# macaron.net
KiCad netlist of a schematic drawn in EAGLE
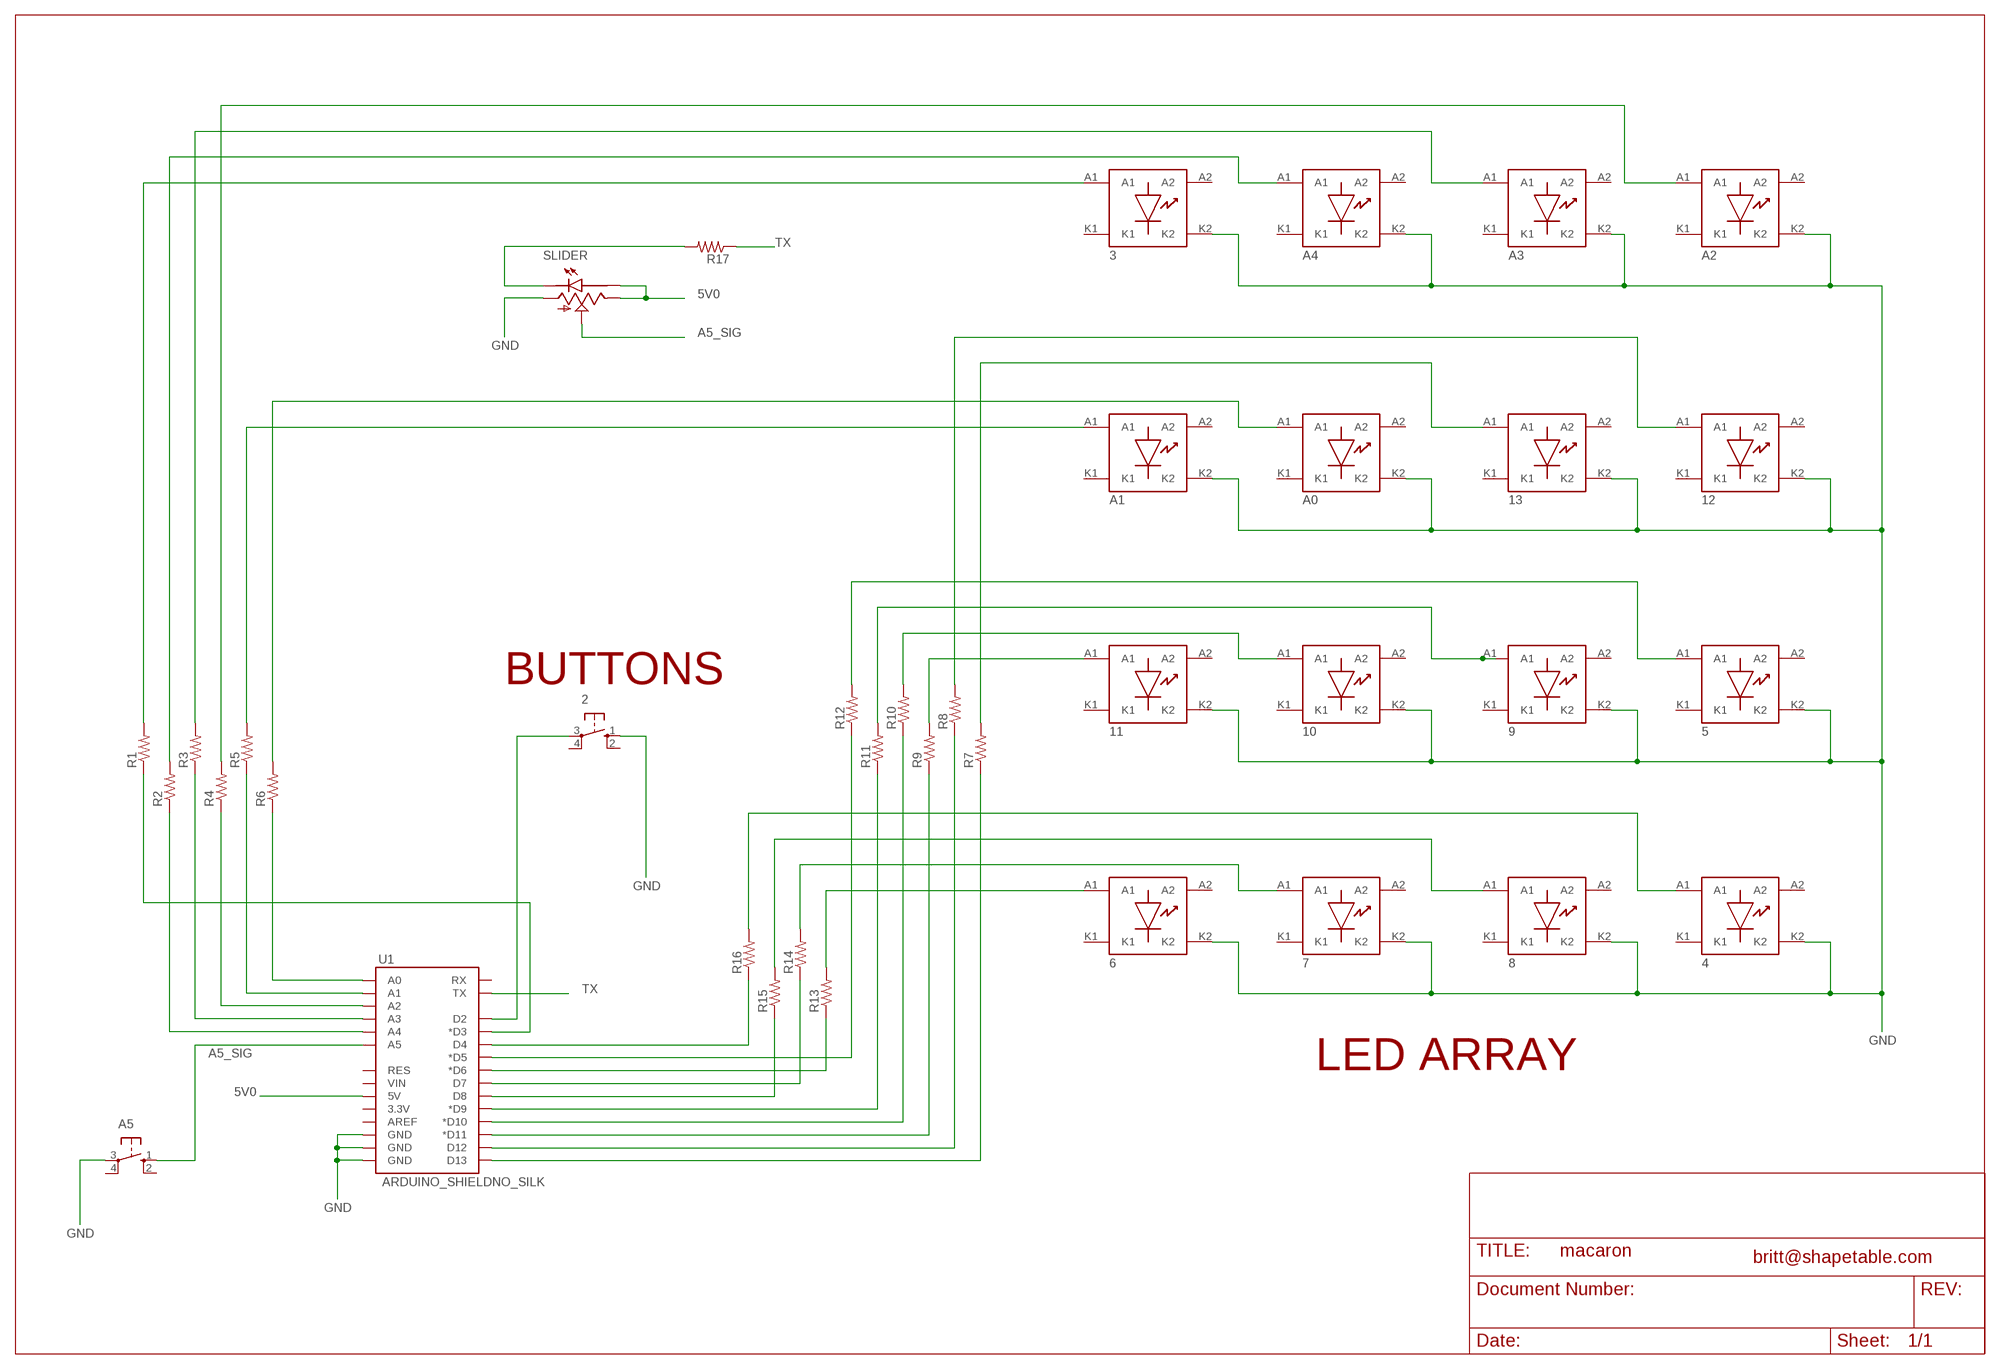
[diagram p0: schematic, sheet 1]

(export (version "E")
  (design (tool "Eeschema 10.0.6"))
  (components
    (comp (ref "2")
      (value "10-XX")
      (footprint "eagle-import:B3F-10XX")
      (fields (field (name "MPN") "B3F-1000"))
      (libsource (lib "eagle-import") (part "10-XX"))
    )
    (comp (ref "3")
      (value "LED_SMT")
      (footprint "eagle-import:AVAGO-SMT-LED")
      (libsource (lib "eagle-import") (part "LED_SMT"))
    )
    (comp (ref "4")
      (value "LED_SMT")
      (footprint "eagle-import:AVAGO-SMT-LED")
      (libsource (lib "eagle-import") (part "LED_SMT"))
    )
    (comp (ref "5")
      (value "LED_SMT")
      (footprint "eagle-import:AVAGO-SMT-LED")
      (libsource (lib "eagle-import") (part "LED_SMT"))
    )
    (comp (ref "6")
      (value "LED_SMT")
      (footprint "eagle-import:AVAGO-SMT-LED")
      (libsource (lib "eagle-import") (part "LED_SMT"))
    )
    (comp (ref "7")
      (value "LED_SMT")
      (footprint "eagle-import:AVAGO-SMT-LED")
      (libsource (lib "eagle-import") (part "LED_SMT"))
    )
    (comp (ref "8")
      (value "LED_SMT")
      (footprint "eagle-import:AVAGO-SMT-LED")
      (libsource (lib "eagle-import") (part "LED_SMT"))
    )
    (comp (ref "9")
      (value "LED_SMT")
      (footprint "eagle-import:AVAGO-SMT-LED")
      (libsource (lib "eagle-import") (part "LED_SMT"))
    )
    (comp (ref "10")
      (value "LED_SMT")
      (footprint "eagle-import:AVAGO-SMT-LED")
      (libsource (lib "eagle-import") (part "LED_SMT"))
    )
    (comp (ref "11")
      (value "LED_SMT")
      (footprint "eagle-import:AVAGO-SMT-LED")
      (libsource (lib "eagle-import") (part "LED_SMT"))
    )
    (comp (ref "12")
      (value "LED_SMT")
      (footprint "eagle-import:AVAGO-SMT-LED")
      (libsource (lib "eagle-import") (part "LED_SMT"))
    )
    (comp (ref "13")
      (value "LED_SMT")
      (footprint "eagle-import:AVAGO-SMT-LED")
      (libsource (lib "eagle-import") (part "LED_SMT"))
    )
    (comp (ref "A0")
      (value "LED_SMT")
      (footprint "eagle-import:AVAGO-SMT-LED")
      (libsource (lib "eagle-import") (part "LED_SMT"))
    )
    (comp (ref "A1")
      (value "LED_SMT")
      (footprint "eagle-import:AVAGO-SMT-LED")
      (libsource (lib "eagle-import") (part "LED_SMT"))
    )
    (comp (ref "A2")
      (value "LED_SMT")
      (footprint "eagle-import:AVAGO-SMT-LED")
      (libsource (lib "eagle-import") (part "LED_SMT"))
    )
    (comp (ref "A3")
      (value "LED_SMT")
      (footprint "eagle-import:AVAGO-SMT-LED")
      (libsource (lib "eagle-import") (part "LED_SMT"))
    )
    (comp (ref "A4")
      (value "LED_SMT")
      (footprint "eagle-import:AVAGO-SMT-LED")
      (libsource (lib "eagle-import") (part "LED_SMT"))
    )
    (comp (ref "A5")
      (value "10-XX")
      (footprint "eagle-import:B3F-10XX")
      (fields (field (name "MPN") "B3F-1000"))
      (libsource (lib "eagle-import") (part "10-XX"))
    )
    (comp (ref "R1")
      (value "R-US_0204/7")
      (footprint "eagle-import:0204_7")
      (libsource (lib "eagle-import") (part "R-US_0204/7"))
    )
    (comp (ref "R2")
      (value "R-US_0204/7")
      (footprint "eagle-import:0204_7")
      (libsource (lib "eagle-import") (part "R-US_0204/7"))
    )
    (comp (ref "R3")
      (value "R-US_0204/7")
      (footprint "eagle-import:0204_7")
      (libsource (lib "eagle-import") (part "R-US_0204/7"))
    )
    (comp (ref "R4")
      (value "R-US_0204/7")
      (footprint "eagle-import:0204_7")
      (libsource (lib "eagle-import") (part "R-US_0204/7"))
    )
    (comp (ref "R5")
      (value "R-US_0204/7")
      (footprint "eagle-import:0204_7")
      (libsource (lib "eagle-import") (part "R-US_0204/7"))
    )
    (comp (ref "R6")
      (value "R-US_0204/7")
      (footprint "eagle-import:0204_7")
      (libsource (lib "eagle-import") (part "R-US_0204/7"))
    )
    (comp (ref "R7")
      (value "R-US_0204/7")
      (footprint "eagle-import:0204_7")
      (libsource (lib "eagle-import") (part "R-US_0204/7"))
    )
    (comp (ref "R8")
      (value "R-US_0204/7")
      (footprint "eagle-import:0204_7")
      (libsource (lib "eagle-import") (part "R-US_0204/7"))
    )
    (comp (ref "R9")
      (value "R-US_0204/7")
      (footprint "eagle-import:0204_7")
      (libsource (lib "eagle-import") (part "R-US_0204/7"))
    )
    (comp (ref "R10")
      (value "R-US_0204/7")
      (footprint "eagle-import:0204_7")
      (libsource (lib "eagle-import") (part "R-US_0204/7"))
    )
    (comp (ref "R11")
      (value "R-US_0204/7")
      (footprint "eagle-import:0204_7")
      (libsource (lib "eagle-import") (part "R-US_0204/7"))
    )
    (comp (ref "R12")
      (value "R-US_0204/7")
      (footprint "eagle-import:0204_7")
      (libsource (lib "eagle-import") (part "R-US_0204/7"))
    )
    (comp (ref "R13")
      (value "R-US_0204/7")
      (footprint "eagle-import:0204_7")
      (libsource (lib "eagle-import") (part "R-US_0204/7"))
    )
    (comp (ref "R14")
      (value "R-US_0204/7")
      (footprint "eagle-import:0204_7")
      (libsource (lib "eagle-import") (part "R-US_0204/7"))
    )
    (comp (ref "R15")
      (value "R-US_0204/7")
      (footprint "eagle-import:0204_7")
      (libsource (lib "eagle-import") (part "R-US_0204/7"))
    )
    (comp (ref "R16")
      (value "R-US_0204/7")
      (footprint "eagle-import:0204_7")
      (libsource (lib "eagle-import") (part "R-US_0204/7"))
    )
    (comp (ref "R17")
      (value "R-US_0204/7")
      (footprint "eagle-import:0204_7")
      (libsource (lib "eagle-import") (part "R-US_0204/7"))
    )
    (comp (ref "SLIDER")
      (value "BOURNS_LED_SLIDER")
      (footprint "eagle-import:BOURNS_45MM_LED_SLIDE_POT")
      (libsource (lib "eagle-import") (part "BOURNS_LED_SLIDER"))
    )
    (comp (ref "U1")
      (value "ARDUINO_SHIELDNO_SILK")
      (footprint "eagle-import:DUEMILANOVE_VIAS")
      (libsource (lib "eagle-import") (part "ARDUINO_SHIELDNO_SILK"))
    )
  )
  (nets
    (net (code "1") (name "/5V0") (class "Default")
      (node (ref "SLIDER") (pin "HIGH_END") (pinfunction "HIGH_HIGH_END") (pintype "passive"))
      (node (ref "SLIDER") (pin "LED+") (pinfunction "A1_LED+") (pintype "passive"))
      (node (ref "U1") (pin "5V") (pinfunction "5V_5V") (pintype "bidirectional"))
    )
    (net (code "2") (name "/A5_SIG") (class "Default")
      (node (ref "A5") (pin "1") (pinfunction "S_1") (pintype "passive"))
      (node (ref "SLIDER") (pin "WIPER") (pinfunction "WIPER_WIPER") (pintype "passive"))
      (node (ref "U1") (pin "A5") (pinfunction "A5_A5") (pintype "bidirectional"))
    )
    (net (code "3") (name "/GND") (class "Default")
      (node (ref "10") (pin "K2") (pinfunction "K2_K2") (pintype "passive"))
      (node (ref "11") (pin "K2") (pinfunction "K2_K2") (pintype "passive"))
      (node (ref "12") (pin "K2") (pinfunction "K2_K2") (pintype "passive"))
      (node (ref "13") (pin "K2") (pinfunction "K2_K2") (pintype "passive"))
      (node (ref "2") (pin "1") (pinfunction "S_1") (pintype "passive"))
      (node (ref "3") (pin "K2") (pinfunction "K2_K2") (pintype "passive"))
      (node (ref "4") (pin "K2") (pinfunction "K2_K2") (pintype "passive"))
      (node (ref "5") (pin "K2") (pinfunction "K2_K2") (pintype "passive"))
      (node (ref "6") (pin "K2") (pinfunction "K2_K2") (pintype "passive"))
      (node (ref "7") (pin "K2") (pinfunction "K2_K2") (pintype "passive"))
      (node (ref "8") (pin "K2") (pinfunction "K2_K2") (pintype "passive"))
      (node (ref "9") (pin "K2") (pinfunction "K2_K2") (pintype "passive"))
      (node (ref "A0") (pin "K2") (pinfunction "K2_K2") (pintype "passive"))
      (node (ref "A1") (pin "K2") (pinfunction "K2_K2") (pintype "passive"))
      (node (ref "A2") (pin "K2") (pinfunction "K2_K2") (pintype "passive"))
      (node (ref "A3") (pin "K2") (pinfunction "K2_K2") (pintype "passive"))
      (node (ref "A4") (pin "K2") (pinfunction "K2_K2") (pintype "passive"))
      (node (ref "A5") (pin "3") (pinfunction "P_3") (pintype "passive"))
      (node (ref "SLIDER") (pin "LOW_END") (pinfunction "LOW_LOW_END") (pintype "passive"))
      (node (ref "U1") (pin "GND@0") (pinfunction "GND_GND@0") (pintype "bidirectional"))
      (node (ref "U1") (pin "GND@1") (pinfunction "GND_GND@1") (pintype "bidirectional"))
      (node (ref "U1") (pin "GND@2") (pinfunction "GND_GND@2") (pintype "bidirectional"))
    )
    (net (code "4") (name "/TX") (class "Default")
      (node (ref "R17") (pin "1") (pinfunction "1_1") (pintype "passive"))
      (node (ref "U1") (pin "TX") (pinfunction "TX_TX") (pintype "bidirectional"))
    )
    (net (code "5") (name "Net-(2-P)") (class "Default")
      (node (ref "2") (pin "3") (pinfunction "P_3") (pintype "passive"))
      (node (ref "U1") (pin "D2") (pinfunction "D2_D2") (pintype "bidirectional"))
    )
    (net (code "6") (name "Net-(3-PadA1)") (class "Default")
      (node (ref "3") (pin "A1") (pinfunction "A1_A1") (pintype "passive"))
      (node (ref "R1") (pin "2") (pinfunction "2_2") (pintype "passive"))
    )
    (net (code "7") (name "Net-(4-PadA1)") (class "Default")
      (node (ref "4") (pin "A1") (pinfunction "A1_A1") (pintype "passive"))
      (node (ref "R16") (pin "2") (pinfunction "2_2") (pintype "passive"))
    )
    (net (code "8") (name "Net-(5-PadA1)") (class "Default")
      (node (ref "5") (pin "A1") (pinfunction "A1_A1") (pintype "passive"))
      (node (ref "R12") (pin "2") (pinfunction "2_2") (pintype "passive"))
    )
    (net (code "9") (name "Net-(6-PadA1)") (class "Default")
      (node (ref "6") (pin "A1") (pinfunction "A1_A1") (pintype "passive"))
      (node (ref "R13") (pin "2") (pinfunction "2_2") (pintype "passive"))
    )
    (net (code "10") (name "Net-(7-PadA1)") (class "Default")
      (node (ref "7") (pin "A1") (pinfunction "A1_A1") (pintype "passive"))
      (node (ref "R14") (pin "2") (pinfunction "2_2") (pintype "passive"))
    )
    (net (code "11") (name "Net-(8-PadA1)") (class "Default")
      (node (ref "8") (pin "A1") (pinfunction "A1_A1") (pintype "passive"))
      (node (ref "R15") (pin "2") (pinfunction "2_2") (pintype "passive"))
    )
    (net (code "12") (name "Net-(9-PadA1)") (class "Default")
      (node (ref "9") (pin "A1") (pinfunction "A1_A1") (pintype "passive"))
      (node (ref "R11") (pin "2") (pinfunction "2_2") (pintype "passive"))
    )
    (net (code "13") (name "Net-(10-PadA1)") (class "Default")
      (node (ref "10") (pin "A1") (pinfunction "A1_A1") (pintype "passive"))
      (node (ref "R10") (pin "2") (pinfunction "2_2") (pintype "passive"))
    )
    (net (code "14") (name "Net-(11-PadA1)") (class "Default")
      (node (ref "11") (pin "A1") (pinfunction "A1_A1") (pintype "passive"))
      (node (ref "R9") (pin "2") (pinfunction "2_2") (pintype "passive"))
    )
    (net (code "15") (name "Net-(12-PadA1)") (class "Default")
      (node (ref "12") (pin "A1") (pinfunction "A1_A1") (pintype "passive"))
      (node (ref "R8") (pin "2") (pinfunction "2_2") (pintype "passive"))
    )
    (net (code "16") (name "Net-(13-PadA1)") (class "Default")
      (node (ref "13") (pin "A1") (pinfunction "A1_A1") (pintype "passive"))
      (node (ref "R7") (pin "2") (pinfunction "2_2") (pintype "passive"))
    )
    (net (code "17") (name "Net-(A0-PadA1)") (class "Default")
      (node (ref "A0") (pin "A1") (pinfunction "A1_A1") (pintype "passive"))
      (node (ref "R6") (pin "2") (pinfunction "2_2") (pintype "passive"))
    )
    (net (code "18") (name "Net-(A1-PadA1)") (class "Default")
      (node (ref "A1") (pin "A1") (pinfunction "A1_A1") (pintype "passive"))
      (node (ref "R5") (pin "2") (pinfunction "2_2") (pintype "passive"))
    )
    (net (code "19") (name "Net-(A2-PadA1)") (class "Default")
      (node (ref "A2") (pin "A1") (pinfunction "A1_A1") (pintype "passive"))
      (node (ref "R4") (pin "2") (pinfunction "2_2") (pintype "passive"))
    )
    (net (code "20") (name "Net-(A3-PadA1)") (class "Default")
      (node (ref "A3") (pin "A1") (pinfunction "A1_A1") (pintype "passive"))
      (node (ref "R3") (pin "2") (pinfunction "2_2") (pintype "passive"))
    )
    (net (code "21") (name "Net-(A4-PadA1)") (class "Default")
      (node (ref "A4") (pin "A1") (pinfunction "A1_A1") (pintype "passive"))
      (node (ref "R2") (pin "2") (pinfunction "2_2") (pintype "passive"))
    )
    (net (code "22") (name "Net-(R2-Pad1)") (class "Default")
      (node (ref "R2") (pin "1") (pinfunction "1_1") (pintype "passive"))
      (node (ref "U1") (pin "A4") (pinfunction "A4_A4") (pintype "bidirectional"))
    )
    (net (code "23") (name "Net-(R3-Pad1)") (class "Default")
      (node (ref "R3") (pin "1") (pinfunction "1_1") (pintype "passive"))
      (node (ref "U1") (pin "A3") (pinfunction "A3_A3") (pintype "bidirectional"))
    )
    (net (code "24") (name "Net-(R4-Pad1)") (class "Default")
      (node (ref "R4") (pin "1") (pinfunction "1_1") (pintype "passive"))
      (node (ref "U1") (pin "A2") (pinfunction "A2_A2") (pintype "bidirectional"))
    )
    (net (code "25") (name "Net-(R5-Pad1)") (class "Default")
      (node (ref "R5") (pin "1") (pinfunction "1_1") (pintype "passive"))
      (node (ref "U1") (pin "A1") (pinfunction "A1_A1") (pintype "bidirectional"))
    )
    (net (code "26") (name "Net-(R6-Pad1)") (class "Default")
      (node (ref "R6") (pin "1") (pinfunction "1_1") (pintype "passive"))
      (node (ref "U1") (pin "A0") (pinfunction "A0_A0") (pintype "bidirectional"))
    )
    (net (code "27") (name "Net-(R7-Pad1)") (class "Default")
      (node (ref "R7") (pin "1") (pinfunction "1_1") (pintype "passive"))
      (node (ref "U1") (pin "D13") (pinfunction "D13_D13") (pintype "bidirectional"))
    )
    (net (code "28") (name "Net-(R8-Pad1)") (class "Default")
      (node (ref "R8") (pin "1") (pinfunction "1_1") (pintype "passive"))
      (node (ref "U1") (pin "D12") (pinfunction "D12_D12") (pintype "bidirectional"))
    )
    (net (code "29") (name "Net-(R14-Pad1)") (class "Default")
      (node (ref "R14") (pin "1") (pinfunction "1_1") (pintype "passive"))
      (node (ref "U1") (pin "D7") (pinfunction "D7_D7") (pintype "bidirectional"))
    )
    (net (code "30") (name "Net-(R15-Pad1)") (class "Default")
      (node (ref "R15") (pin "1") (pinfunction "1_1") (pintype "passive"))
      (node (ref "U1") (pin "D8") (pinfunction "D8_D8") (pintype "bidirectional"))
    )
    (net (code "31") (name "Net-(R16-Pad1)") (class "Default")
      (node (ref "R16") (pin "1") (pinfunction "1_1") (pintype "passive"))
      (node (ref "U1") (pin "D4") (pinfunction "D4_D4") (pintype "bidirectional"))
    )
    (net (code "32") (name "Net-(SLIDER-C)") (class "Default")
      (node (ref "R17") (pin "2") (pinfunction "2_2") (pintype "passive"))
      (node (ref "SLIDER") (pin "LED-") (pinfunction "C_LED-") (pintype "passive"))
    )
    (net (code "33") (name "Net-(U1-*D3)") (class "Default")
      (node (ref "R1") (pin "1") (pinfunction "1_1") (pintype "passive"))
      (node (ref "U1") (pin "D3") (pinfunction "*D3_D3") (pintype "bidirectional"))
    )
    (net (code "34") (name "Net-(U1-*D5)") (class "Default")
      (node (ref "R12") (pin "1") (pinfunction "1_1") (pintype "passive"))
      (node (ref "U1") (pin "D5") (pinfunction "*D5_D5") (pintype "bidirectional"))
    )
    (net (code "35") (name "Net-(U1-*D6)") (class "Default")
      (node (ref "R13") (pin "1") (pinfunction "1_1") (pintype "passive"))
      (node (ref "U1") (pin "D6") (pinfunction "*D6_D6") (pintype "bidirectional"))
    )
    (net (code "36") (name "Net-(U1-*D9)") (class "Default")
      (node (ref "R11") (pin "1") (pinfunction "1_1") (pintype "passive"))
      (node (ref "U1") (pin "D9") (pinfunction "*D9_D9") (pintype "bidirectional"))
    )
    (net (code "37") (name "Net-(U1-*D10)") (class "Default")
      (node (ref "R10") (pin "1") (pinfunction "1_1") (pintype "passive"))
      (node (ref "U1") (pin "D10") (pinfunction "*D10_D10") (pintype "bidirectional"))
    )
    (net (code "38") (name "Net-(U1-*D11)") (class "Default")
      (node (ref "R9") (pin "1") (pinfunction "1_1") (pintype "passive"))
      (node (ref "U1") (pin "D11") (pinfunction "*D11_D11") (pintype "bidirectional"))
    )
    (net (code "39") (name "unconnected-(2-P1-Pad4)") (class "Default")
      (node (ref "2") (pin "4") (pinfunction "P1_4") (pintype "passive"))
    )
    (net (code "40") (name "unconnected-(2-S1-Pad2)") (class "Default")
      (node (ref "2") (pin "2") (pinfunction "S1_2") (pintype "passive"))
    )
    (net (code "41") (name "unconnected-(3-PadA2)") (class "Default")
      (node (ref "3") (pin "A2") (pinfunction "A2_A2") (pintype "passive"))
    )
    (net (code "42") (name "unconnected-(3-PadK1)") (class "Default")
      (node (ref "3") (pin "K1") (pinfunction "K1_K1") (pintype "passive"))
    )
    (net (code "43") (name "unconnected-(4-PadA2)") (class "Default")
      (node (ref "4") (pin "A2") (pinfunction "A2_A2") (pintype "passive"))
    )
    (net (code "44") (name "unconnected-(4-PadK1)") (class "Default")
      (node (ref "4") (pin "K1") (pinfunction "K1_K1") (pintype "passive"))
    )
    (net (code "45") (name "unconnected-(5-PadA2)") (class "Default")
      (node (ref "5") (pin "A2") (pinfunction "A2_A2") (pintype "passive"))
    )
    (net (code "46") (name "unconnected-(5-PadK1)") (class "Default")
      (node (ref "5") (pin "K1") (pinfunction "K1_K1") (pintype "passive"))
    )
    (net (code "47") (name "unconnected-(6-PadA2)") (class "Default")
      (node (ref "6") (pin "A2") (pinfunction "A2_A2") (pintype "passive"))
    )
    (net (code "48") (name "unconnected-(6-PadK1)") (class "Default")
      (node (ref "6") (pin "K1") (pinfunction "K1_K1") (pintype "passive"))
    )
    (net (code "49") (name "unconnected-(7-PadA2)") (class "Default")
      (node (ref "7") (pin "A2") (pinfunction "A2_A2") (pintype "passive"))
    )
    (net (code "50") (name "unconnected-(7-PadK1)") (class "Default")
      (node (ref "7") (pin "K1") (pinfunction "K1_K1") (pintype "passive"))
    )
    (net (code "51") (name "unconnected-(8-PadA2)") (class "Default")
      (node (ref "8") (pin "A2") (pinfunction "A2_A2") (pintype "passive"))
    )
    (net (code "52") (name "unconnected-(8-PadK1)") (class "Default")
      (node (ref "8") (pin "K1") (pinfunction "K1_K1") (pintype "passive"))
    )
    (net (code "53") (name "unconnected-(9-PadA2)") (class "Default")
      (node (ref "9") (pin "A2") (pinfunction "A2_A2") (pintype "passive"))
    )
    (net (code "54") (name "unconnected-(9-PadK1)") (class "Default")
      (node (ref "9") (pin "K1") (pinfunction "K1_K1") (pintype "passive"))
    )
    (net (code "55") (name "unconnected-(10-PadA2)") (class "Default")
      (node (ref "10") (pin "A2") (pinfunction "A2_A2") (pintype "passive"))
    )
    (net (code "56") (name "unconnected-(10-PadK1)") (class "Default")
      (node (ref "10") (pin "K1") (pinfunction "K1_K1") (pintype "passive"))
    )
    (net (code "57") (name "unconnected-(11-PadA2)") (class "Default")
      (node (ref "11") (pin "A2") (pinfunction "A2_A2") (pintype "passive"))
    )
    (net (code "58") (name "unconnected-(11-PadK1)") (class "Default")
      (node (ref "11") (pin "K1") (pinfunction "K1_K1") (pintype "passive"))
    )
    (net (code "59") (name "unconnected-(12-PadA2)") (class "Default")
      (node (ref "12") (pin "A2") (pinfunction "A2_A2") (pintype "passive"))
    )
    (net (code "60") (name "unconnected-(12-PadK1)") (class "Default")
      (node (ref "12") (pin "K1") (pinfunction "K1_K1") (pintype "passive"))
    )
    (net (code "61") (name "unconnected-(13-PadA2)") (class "Default")
      (node (ref "13") (pin "A2") (pinfunction "A2_A2") (pintype "passive"))
    )
    (net (code "62") (name "unconnected-(13-PadK1)") (class "Default")
      (node (ref "13") (pin "K1") (pinfunction "K1_K1") (pintype "passive"))
    )
    (net (code "63") (name "unconnected-(A0-PadA2)") (class "Default")
      (node (ref "A0") (pin "A2") (pinfunction "A2_A2") (pintype "passive"))
    )
    (net (code "64") (name "unconnected-(A0-PadK1)") (class "Default")
      (node (ref "A0") (pin "K1") (pinfunction "K1_K1") (pintype "passive"))
    )
    (net (code "65") (name "unconnected-(A1-PadA2)") (class "Default")
      (node (ref "A1") (pin "A2") (pinfunction "A2_A2") (pintype "passive"))
    )
    (net (code "66") (name "unconnected-(A1-PadK1)") (class "Default")
      (node (ref "A1") (pin "K1") (pinfunction "K1_K1") (pintype "passive"))
    )
    (net (code "67") (name "unconnected-(A2-PadA2)") (class "Default")
      (node (ref "A2") (pin "A2") (pinfunction "A2_A2") (pintype "passive"))
    )
    (net (code "68") (name "unconnected-(A2-PadK1)") (class "Default")
      (node (ref "A2") (pin "K1") (pinfunction "K1_K1") (pintype "passive"))
    )
    (net (code "69") (name "unconnected-(A3-PadA2)") (class "Default")
      (node (ref "A3") (pin "A2") (pinfunction "A2_A2") (pintype "passive"))
    )
    (net (code "70") (name "unconnected-(A3-PadK1)") (class "Default")
      (node (ref "A3") (pin "K1") (pinfunction "K1_K1") (pintype "passive"))
    )
    (net (code "71") (name "unconnected-(A4-PadA2)") (class "Default")
      (node (ref "A4") (pin "A2") (pinfunction "A2_A2") (pintype "passive"))
    )
    (net (code "72") (name "unconnected-(A4-PadK1)") (class "Default")
      (node (ref "A4") (pin "K1") (pinfunction "K1_K1") (pintype "passive"))
    )
    (net (code "73") (name "unconnected-(A5-P1-Pad4)") (class "Default")
      (node (ref "A5") (pin "4") (pinfunction "P1_4") (pintype "passive"))
    )
    (net (code "74") (name "unconnected-(A5-S1-Pad2)") (class "Default")
      (node (ref "A5") (pin "2") (pinfunction "S1_2") (pintype "passive"))
    )
    (net (code "75") (name "unconnected-(U1-Pad3.3V)") (class "Default")
      (node (ref "U1") (pin "3.3V") (pinfunction "3.3V_3.3V") (pintype "bidirectional"))
    )
    (net (code "76") (name "unconnected-(U1-PadAREF)") (class "Default")
      (node (ref "U1") (pin "AREF") (pinfunction "AREF_AREF") (pintype "bidirectional"))
    )
    (net (code "77") (name "unconnected-(U1-PadRES)") (class "Default")
      (node (ref "U1") (pin "RES") (pinfunction "RES_RES") (pintype "bidirectional"))
    )
    (net (code "78") (name "unconnected-(U1-PadRX)") (class "Default")
      (node (ref "U1") (pin "RX") (pinfunction "RX_RX") (pintype "bidirectional"))
    )
    (net (code "79") (name "unconnected-(U1-PadVIN)") (class "Default")
      (node (ref "U1") (pin "VIN") (pinfunction "VIN_VIN") (pintype "bidirectional"))
    )
  )
)
